# power_supply.net
KiCad netlist of a schematic drawn in Altium Designer
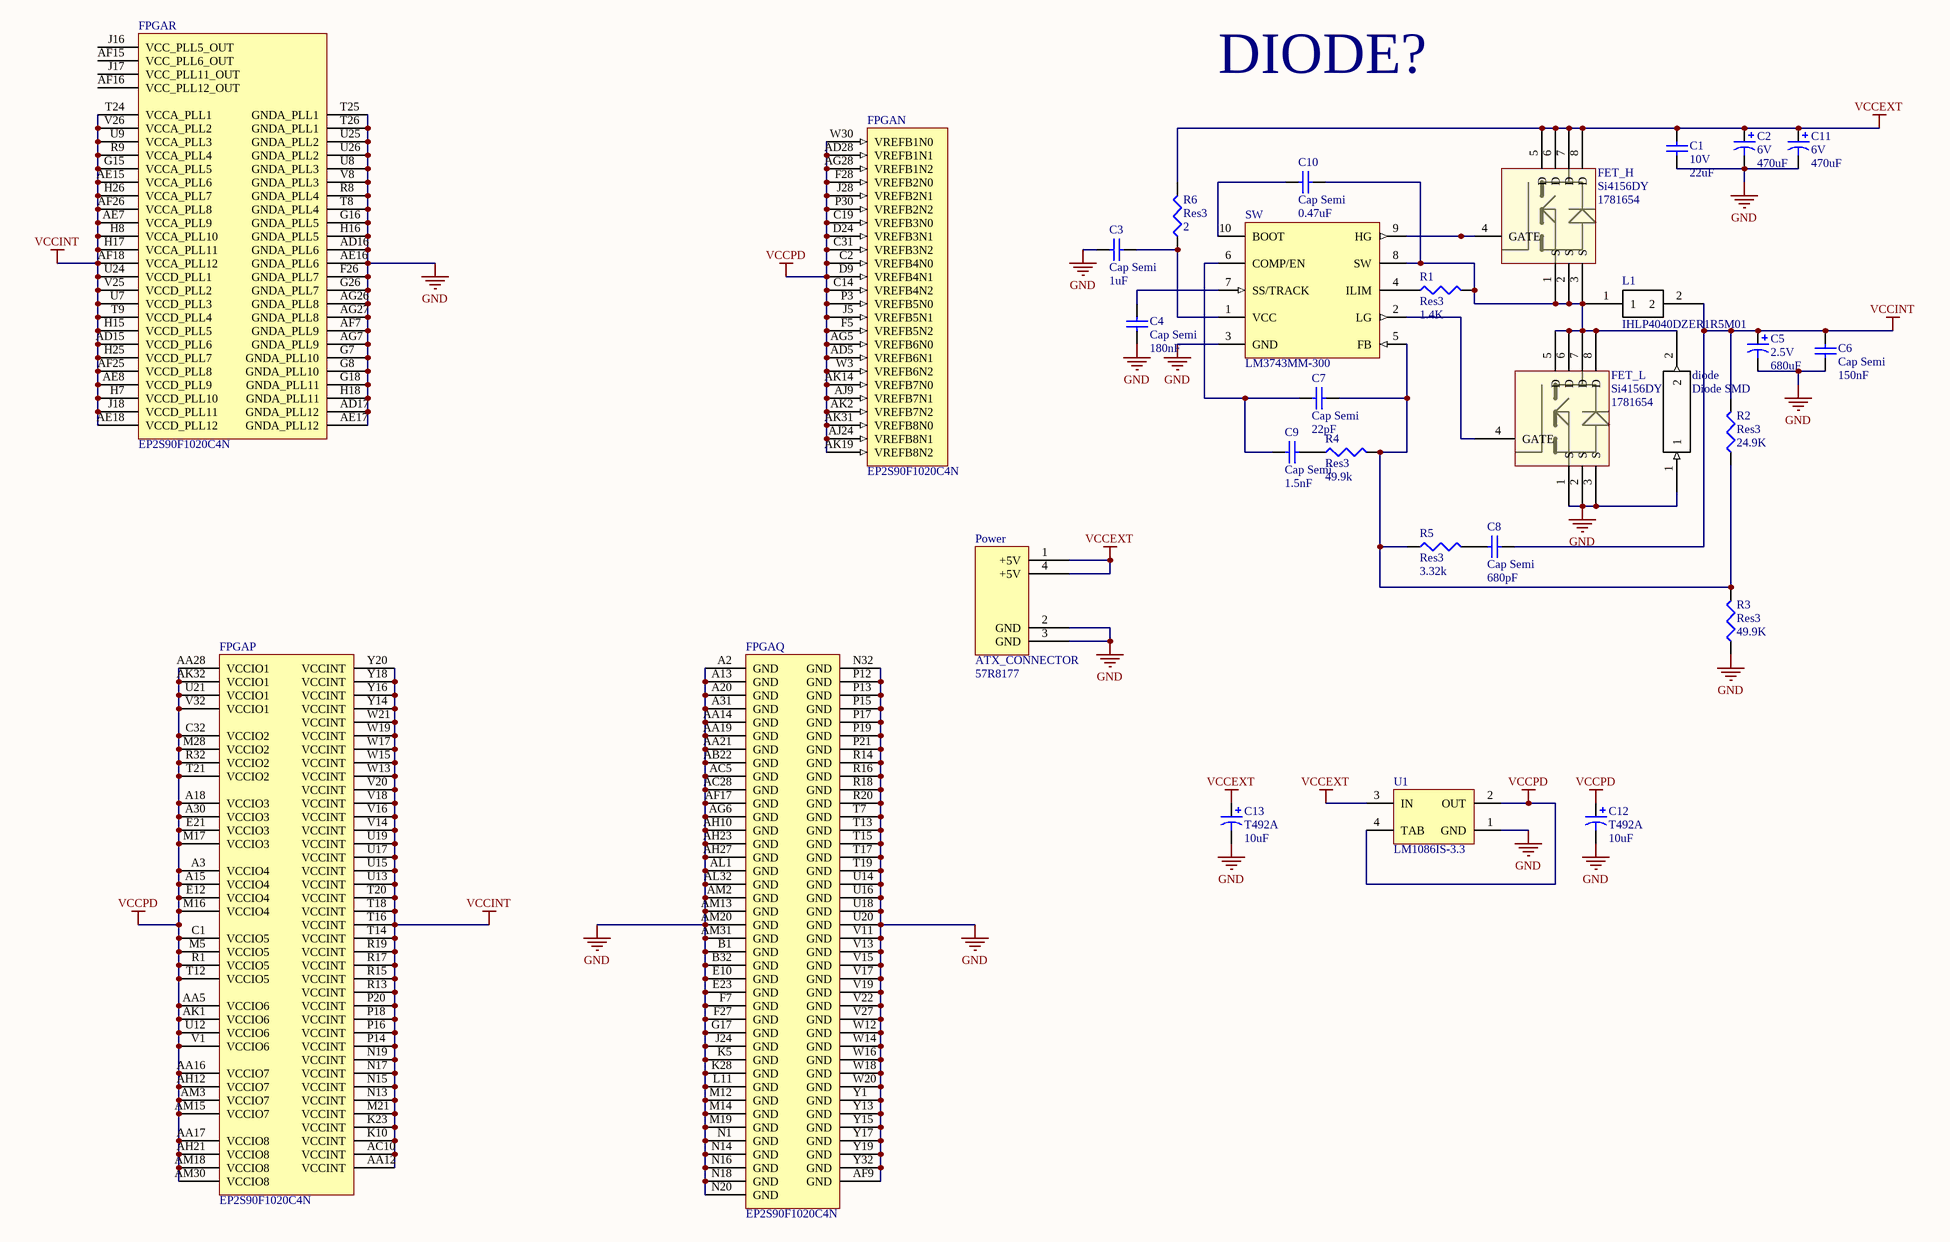
[diagram p0: power_supply.SchDoc]

(export (version "E")
  (design (tool "Eeschema 10.0.6"))
  (components
    (comp (ref "C1")
      (value "10V")
      (footprint "CAPC3225L")
      (description "Capacitor (Semiconductor SIM Model)")
      (fields (field (name "ALTIUM_VALUE") "22uF") (field (name "PUBLISHER") "Altium Limited"))
      (libsource (lib "Miscellaneous Devices") (part "Cap Semi"))
    )
    (comp (ref "C2")
      (value "6V")
      (footprint "KEMET Chip Capacitor:E")
      (description "Polarized Capacitor (Surface Mount)")
      (fields (field (name "ALTIUM_VALUE") "470uF") (field (name "PUBLISHER") "Altium Limited"))
      (libsource (lib "Miscellaneous Devices") (part "Cap Pol3"))
    )
    (comp (ref "C3")
      (value "Cap Semi")
      (footprint "2012[0805]")
      (description "Capacitor (Semiconductor SIM Model)")
      (fields (field (name "ALTIUM_VALUE") "1uF") (field (name "PUBLISHER") "Altium Limited"))
      (libsource (lib "Miscellaneous Devices") (part "Cap Semi"))
    )
    (comp (ref "C4")
      (value "Cap Semi")
      (footprint "2012[0805]")
      (description "Capacitor (Semiconductor SIM Model)")
      (fields (field (name "ALTIUM_VALUE") "180nF") (field (name "PUBLISHER") "Altium Limited"))
      (libsource (lib "Miscellaneous Devices") (part "Cap Semi"))
    )
    (comp (ref "C5")
      (value "2.5V")
      (footprint "E")
      (description "Polarized Capacitor (Surface Mount)")
      (fields (field (name "ALTIUM_VALUE") "680uF") (field (name "PUBLISHER") "Altium Limited"))
      (libsource (lib "Miscellaneous Devices") (part "Cap Pol3"))
    )
    (comp (ref "C6")
      (value "Cap Semi")
      (footprint "2012[0805]")
      (description "Capacitor (Semiconductor SIM Model)")
      (fields (field (name "ALTIUM_VALUE") "150nF") (field (name "PUBLISHER") "Altium Limited"))
      (libsource (lib "Miscellaneous Devices") (part "Cap Semi"))
    )
    (comp (ref "C7")
      (value "Cap Semi")
      (footprint "CAPC1608L")
      (description "Capacitor (Semiconductor SIM Model)")
      (fields (field (name "ALTIUM_VALUE") "22pF") (field (name "PUBLISHER") "Altium Limited"))
      (libsource (lib "Miscellaneous Devices") (part "Cap Semi"))
    )
    (comp (ref "C8")
      (value "Cap Semi")
      (footprint "CAPC1608L")
      (description "Capacitor (Semiconductor SIM Model)")
      (fields (field (name "ALTIUM_VALUE") "680pF") (field (name "PUBLISHER") "Altium Limited"))
      (libsource (lib "Miscellaneous Devices") (part "Cap Semi"))
    )
    (comp (ref "C9")
      (value "Cap Semi")
      (footprint "CAPC1608L")
      (description "Capacitor (Semiconductor SIM Model)")
      (fields (field (name "ALTIUM_VALUE") "1.5nF") (field (name "PUBLISHER") "Altium Limited"))
      (libsource (lib "Miscellaneous Devices") (part "Cap Semi"))
    )
    (comp (ref "C10")
      (value "Cap Semi")
      (footprint "2012[0805]")
      (description "Capacitor (Semiconductor SIM Model)")
      (fields (field (name "ALTIUM_VALUE") "0.47uF") (field (name "PUBLISHER") "Altium Limited"))
      (libsource (lib "Miscellaneous Devices") (part "Cap Semi"))
    )
    (comp (ref "C11")
      (value "6V")
      (footprint "E")
      (description "Polarized Capacitor (Surface Mount)")
      (fields (field (name "ALTIUM_VALUE") "470uF") (field (name "PUBLISHER") "Altium Limited"))
      (libsource (lib "Miscellaneous Devices") (part "Cap Pol3"))
    )
    (comp (ref "C12")
      (value "T492A")
      (footprint "A")
      (description "Solid Tantalum Chip Capacitor, T492 Series - CWR11 Style Per Mil-PRF-55365/8")
      (fields (field (name "ALTIUM_VALUE") "10uF") (field (name "PUBLISHER") "Altium Limited"))
      (libsource (lib "KEMET Chip Capacitor") (part "T492A"))
    )
    (comp (ref "C13")
      (value "T492A")
      (footprint "A")
      (description "Solid Tantalum Chip Capacitor, T492 Series - CWR11 Style Per Mil-PRF-55365/8")
      (fields (field (name "ALTIUM_VALUE") "10uF") (field (name "PUBLISHER") "Altium Limited"))
      (libsource (lib "KEMET Chip Capacitor") (part "T492A"))
    )
    (comp (ref "diode")
      (value "Diode SMD")
      (footprint "Diode SMD")
      (libsource (lib "Schematic Components") (part "Diode SMD"))
    )
    (comp (ref "FET_H")
      (value "Si4156DY")
      (footprint "SO-8C_M")
      (fields (field (name "SUPPLIER PART NUMBER 1") "1781654"))
      (libsource (lib "Schematic Components") (part "Si4156DY"))
    )
    (comp (ref "FET_L")
      (value "Si4156DY")
      (footprint "SO-8C_M")
      (fields (field (name "SUPPLIER PART NUMBER 1") "1781654"))
      (libsource (lib "Schematic Components") (part "Si4156DY"))
    )
    (comp (ref "FPGA")
      (value "EP2S90F1020C4N")
      (footprint "FBGA1020")
      (description "Stratix II 1.2V FPGA, 758 I/Os, 1020-Pin FineLine BGA, Speed Grade 4, Commercial Grade, Pb-Free")
      (fields (field (name "PUBLISHER") "Altium Limited"))
      (libsource (lib "Altera Stratix II") (part "EP2S90F1020C4N"))
    )
    (comp (ref "L1")
      (value "IHLP4040DZER1R5M01")
      (footprint "IHLP4040DZER1R5M01")
      (libsource (lib "Schematic Components") (part "IHLP4040DZER1R5M01"))
    )
    (comp (ref "Power")
      (value "ATX_CONNECTOR")
      (footprint "Molex 8981")
      (fields (field (name "SUPPLIER PART NUMBER 1") "57R8177"))
      (libsource (lib "Schematic Components") (part "ATX_CONNECTOR"))
    )
    (comp (ref "R1")
      (value "Res3")
      (footprint "RESC1608L")
      (description "Resistor")
      (fields (field (name "ALTIUM_VALUE") "1.4K") (field (name "PUBLISHER") "Altium Limited"))
      (libsource (lib "Miscellaneous Devices") (part "Res3"))
    )
    (comp (ref "R2")
      (value "Res3")
      (footprint "RESC1608L")
      (description "Resistor")
      (fields (field (name "ALTIUM_VALUE") "24.9K") (field (name "PUBLISHER") "Altium Limited"))
      (libsource (lib "Miscellaneous Devices") (part "Res3"))
    )
    (comp (ref "R3")
      (value "Res3")
      (footprint "RESC1608L")
      (description "Resistor")
      (fields (field (name "ALTIUM_VALUE") "49.9K") (field (name "PUBLISHER") "Altium Limited"))
      (libsource (lib "Miscellaneous Devices") (part "Res3"))
    )
    (comp (ref "R4")
      (value "Res3")
      (footprint "RESC1608L")
      (description "Resistor")
      (fields (field (name "ALTIUM_VALUE") "49.9k") (field (name "PUBLISHER") "Altium Limited"))
      (libsource (lib "Miscellaneous Devices") (part "Res3"))
    )
    (comp (ref "R5")
      (value "Res3")
      (footprint "RESC1608L")
      (description "Resistor")
      (fields (field (name "ALTIUM_VALUE") "3.32k") (field (name "PUBLISHER") "Altium Limited"))
      (libsource (lib "Miscellaneous Devices") (part "Res3"))
    )
    (comp (ref "R6")
      (value "Res3")
      (footprint "RESC1608L")
      (description "Resistor")
      (fields (field (name "ALTIUM_VALUE") "2") (field (name "PUBLISHER") "Altium Limited"))
      (libsource (lib "Miscellaneous Devices") (part "Res3"))
    )
    (comp (ref "SW")
      (value "LM3743MM-300")
      (footprint "MUB10A_N")
      (description "High-Performance Synchronous Buck Controller with Comprehensive Fault Protection Features")
      (fields
        (field (name "MANUFACTURER") "National Semiconductor")
        (field (name "DIGIKEYPARTNUMBER") "LM3743MM-300CT-ND")
        (field (name "PUBLISHER") "Altium Limited")
      )
      (libsource (lib "NSC Switcher") (part "LM3743MM-300"))
    )
    (comp (ref "U1")
      (value "LM1086IS-3.3")
      (footprint "TS3B_N")
      (description "1.5A Low Dropout Positive Regulators")
      (fields
        (field (name "MANUFACTURER") "National Semiconductor")
        (field (name "DIGIKEYPARTNUMBER") "LM1086IS-3.3-ND")
        (field (name "PUBLISHER") "Altium Limited")
      )
      (libsource (lib "NSC LDO") (part "LM1086IS-3.3"))
    )
  )
  (nets
    (net (code "1") (name "GND") (class "Default")
      (node (ref "C1") (pin "2") (pinfunction "2_2") (pintype "passive"))
      (node (ref "C11") (pin "2") (pinfunction "2_2") (pintype "passive"))
      (node (ref "C12") (pin "2") (pinfunction "2_2") (pintype "passive"))
      (node (ref "C13") (pin "2") (pinfunction "2_2") (pintype "passive"))
      (node (ref "C2") (pin "2") (pinfunction "2_2") (pintype "passive"))
      (node (ref "C3") (pin "2") (pinfunction "2_2") (pintype "passive"))
      (node (ref "C4") (pin "1") (pinfunction "1_1") (pintype "passive"))
      (node (ref "C5") (pin "2") (pinfunction "2_2") (pintype "passive"))
      (node (ref "C6") (pin "1") (pinfunction "1_1") (pintype "passive"))
      (node (ref "FET_L") (pin "1") (pinfunction "S_1") (pintype "passive"))
      (node (ref "FET_L") (pin "2") (pinfunction "S_2") (pintype "passive"))
      (node (ref "FET_L") (pin "3") (pinfunction "S_3") (pintype "passive"))
      (node (ref "FPGA") (pin "A13") (pinfunction "GND_A13") (pintype "power_in"))
      (node (ref "FPGA") (pin "A2") (pinfunction "GND_A2") (pintype "power_in"))
      (node (ref "FPGA") (pin "A20") (pinfunction "GND_A20") (pintype "power_in"))
      (node (ref "FPGA") (pin "A31") (pinfunction "GND_A31") (pintype "power_in"))
      (node (ref "FPGA") (pin "AA14") (pinfunction "GND_AA14") (pintype "power_in"))
      (node (ref "FPGA") (pin "AA19") (pinfunction "GND_AA19") (pintype "power_in"))
      (node (ref "FPGA") (pin "AA21") (pinfunction "GND_AA21") (pintype "power_in"))
      (node (ref "FPGA") (pin "AB22") (pinfunction "GND_AB22") (pintype "power_in"))
      (node (ref "FPGA") (pin "AC28") (pinfunction "GND_AC28") (pintype "power_in"))
      (node (ref "FPGA") (pin "AC5") (pinfunction "GND_AC5") (pintype "power_in"))
      (node (ref "FPGA") (pin "AD16") (pinfunction "GNDA_PLL6_AD16") (pintype "power_in"))
      (node (ref "FPGA") (pin "AD17") (pinfunction "GNDA_PLL12_AD17") (pintype "power_in"))
      (node (ref "FPGA") (pin "AE16") (pinfunction "GNDA_PLL6_AE16") (pintype "power_in"))
      (node (ref "FPGA") (pin "AE17") (pinfunction "GNDA_PLL12_AE17") (pintype "power_in"))
      (node (ref "FPGA") (pin "AF17") (pinfunction "GND_AF17") (pintype "power_in"))
      (node (ref "FPGA") (pin "AF7") (pinfunction "GNDA_PLL9_AF7") (pintype "power_in"))
      (node (ref "FPGA") (pin "AF9") (pinfunction "GND_AF9") (pintype "power_in"))
      (node (ref "FPGA") (pin "AG26") (pinfunction "GNDA_PLL8_AG26") (pintype "power_in"))
      (node (ref "FPGA") (pin "AG27") (pinfunction "GNDA_PLL8_AG27") (pintype "power_in"))
      (node (ref "FPGA") (pin "AG6") (pinfunction "GND_AG6") (pintype "power_in"))
      (node (ref "FPGA") (pin "AG7") (pinfunction "GNDA_PLL9_AG7") (pintype "power_in"))
      (node (ref "FPGA") (pin "AH10") (pinfunction "GND_AH10") (pintype "power_in"))
      (node (ref "FPGA") (pin "AH23") (pinfunction "GND_AH23") (pintype "power_in"))
      (node (ref "FPGA") (pin "AH27") (pinfunction "GND_AH27") (pintype "power_in"))
      (node (ref "FPGA") (pin "AL1") (pinfunction "GND_AL1") (pintype "power_in"))
      (node (ref "FPGA") (pin "AL32") (pinfunction "GND_AL32") (pintype "power_in"))
      (node (ref "FPGA") (pin "AM13") (pinfunction "GND_AM13") (pintype "power_in"))
      (node (ref "FPGA") (pin "AM2") (pinfunction "GND_AM2") (pintype "power_in"))
      (node (ref "FPGA") (pin "AM20") (pinfunction "GND_AM20") (pintype "power_in"))
      (node (ref "FPGA") (pin "AM31") (pinfunction "GND_AM31") (pintype "power_in"))
      (node (ref "FPGA") (pin "B1") (pinfunction "GND_B1") (pintype "power_in"))
      (node (ref "FPGA") (pin "B32") (pinfunction "GND_B32") (pintype "power_in"))
      (node (ref "FPGA") (pin "E10") (pinfunction "GND_E10") (pintype "power_in"))
      (node (ref "FPGA") (pin "E23") (pinfunction "GND_E23") (pintype "power_in"))
      (node (ref "FPGA") (pin "F26") (pinfunction "GNDA_PLL7_F26") (pintype "power_in"))
      (node (ref "FPGA") (pin "F27") (pinfunction "GND_F27") (pintype "power_in"))
      (node (ref "FPGA") (pin "F7") (pinfunction "GND_F7") (pintype "power_in"))
      (node (ref "FPGA") (pin "G16") (pinfunction "GNDA_PLL5_G16") (pintype "power_in"))
      (node (ref "FPGA") (pin "G17") (pinfunction "GND_G17") (pintype "power_in"))
      (node (ref "FPGA") (pin "G18") (pinfunction "GNDA_PLL11_G18") (pintype "power_in"))
      (node (ref "FPGA") (pin "G26") (pinfunction "GNDA_PLL7_G26") (pintype "power_in"))
      (node (ref "FPGA") (pin "G7") (pinfunction "GNDA_PLL10_G7") (pintype "power_in"))
      (node (ref "FPGA") (pin "G8") (pinfunction "GNDA_PLL10_G8") (pintype "power_in"))
      (node (ref "FPGA") (pin "H16") (pinfunction "GNDA_PLL5_H16") (pintype "power_in"))
      (node (ref "FPGA") (pin "H18") (pinfunction "GNDA_PLL11_H18") (pintype "power_in"))
      (node (ref "FPGA") (pin "J24") (pinfunction "GND_J24") (pintype "power_in"))
      (node (ref "FPGA") (pin "K28") (pinfunction "GND_K28") (pintype "power_in"))
      (node (ref "FPGA") (pin "K5") (pinfunction "GND_K5") (pintype "power_in"))
      (node (ref "FPGA") (pin "L11") (pinfunction "GND_L11") (pintype "power_in"))
      (node (ref "FPGA") (pin "M12") (pinfunction "GND_M12") (pintype "power_in"))
      (node (ref "FPGA") (pin "M14") (pinfunction "GND_M14") (pintype "power_in"))
      (node (ref "FPGA") (pin "M19") (pinfunction "GND_M19") (pintype "power_in"))
      (node (ref "FPGA") (pin "N1") (pinfunction "GND_N1") (pintype "power_in"))
      (node (ref "FPGA") (pin "N14") (pinfunction "GND_N14") (pintype "power_in"))
      (node (ref "FPGA") (pin "N16") (pinfunction "GND_N16") (pintype "power_in"))
      (node (ref "FPGA") (pin "N18") (pinfunction "GND_N18") (pintype "power_in"))
      (node (ref "FPGA") (pin "N20") (pinfunction "GND_N20") (pintype "power_in"))
      (node (ref "FPGA") (pin "N32") (pinfunction "GND_N32") (pintype "power_in"))
      (node (ref "FPGA") (pin "P12") (pinfunction "GND_P12") (pintype "power_in"))
      (node (ref "FPGA") (pin "P13") (pinfunction "GND_P13") (pintype "power_in"))
      (node (ref "FPGA") (pin "P15") (pinfunction "GND_P15") (pintype "power_in"))
      (node (ref "FPGA") (pin "P17") (pinfunction "GND_P17") (pintype "power_in"))
      (node (ref "FPGA") (pin "P19") (pinfunction "GND_P19") (pintype "power_in"))
      (node (ref "FPGA") (pin "P21") (pinfunction "GND_P21") (pintype "power_in"))
      (node (ref "FPGA") (pin "R14") (pinfunction "GND_R14") (pintype "power_in"))
      (node (ref "FPGA") (pin "R16") (pinfunction "GND_R16") (pintype "power_in"))
      (node (ref "FPGA") (pin "R18") (pinfunction "GND_R18") (pintype "power_in"))
      (node (ref "FPGA") (pin "R20") (pinfunction "GND_R20") (pintype "power_in"))
      (node (ref "FPGA") (pin "R8") (pinfunction "GNDA_PLL4_R8") (pintype "power_in"))
      (node (ref "FPGA") (pin "T13") (pinfunction "GND_T13") (pintype "power_in"))
      (node (ref "FPGA") (pin "T15") (pinfunction "GND_T15") (pintype "power_in"))
      (node (ref "FPGA") (pin "T17") (pinfunction "GND_T17") (pintype "power_in"))
      (node (ref "FPGA") (pin "T19") (pinfunction "GND_T19") (pintype "power_in"))
      (node (ref "FPGA") (pin "T25") (pinfunction "GNDA_PLL1_T25") (pintype "power_in"))
      (node (ref "FPGA") (pin "T26") (pinfunction "GNDA_PLL1_T26") (pintype "power_in"))
      (node (ref "FPGA") (pin "T7") (pinfunction "GND_T7") (pintype "power_in"))
      (node (ref "FPGA") (pin "T8") (pinfunction "GNDA_PLL4_T8") (pintype "power_in"))
      (node (ref "FPGA") (pin "U14") (pinfunction "GND_U14") (pintype "power_in"))
      (node (ref "FPGA") (pin "U16") (pinfunction "GND_U16") (pintype "power_in"))
      (node (ref "FPGA") (pin "U18") (pinfunction "GND_U18") (pintype "power_in"))
      (node (ref "FPGA") (pin "U20") (pinfunction "GND_U20") (pintype "power_in"))
      (node (ref "FPGA") (pin "U25") (pinfunction "GNDA_PLL2_U25") (pintype "power_in"))
      (node (ref "FPGA") (pin "U26") (pinfunction "GNDA_PLL2_U26") (pintype "power_in"))
      (node (ref "FPGA") (pin "U8") (pinfunction "GNDA_PLL3_U8") (pintype "power_in"))
      (node (ref "FPGA") (pin "V11") (pinfunction "GND_V11") (pintype "power_in"))
      (node (ref "FPGA") (pin "V13") (pinfunction "GND_V13") (pintype "power_in"))
      (node (ref "FPGA") (pin "V15") (pinfunction "GND_V15") (pintype "power_in"))
      (node (ref "FPGA") (pin "V17") (pinfunction "GND_V17") (pintype "power_in"))
      (node (ref "FPGA") (pin "V19") (pinfunction "GND_V19") (pintype "power_in"))
      (node (ref "FPGA") (pin "V22") (pinfunction "GND_V22") (pintype "power_in"))
      (node (ref "FPGA") (pin "V27") (pinfunction "GND_V27") (pintype "power_in"))
      (node (ref "FPGA") (pin "V8") (pinfunction "GNDA_PLL3_V8") (pintype "power_in"))
      (node (ref "FPGA") (pin "W12") (pinfunction "GND_W12") (pintype "power_in"))
      (node (ref "FPGA") (pin "W14") (pinfunction "GND_W14") (pintype "power_in"))
      (node (ref "FPGA") (pin "W16") (pinfunction "GND_W16") (pintype "power_in"))
      (node (ref "FPGA") (pin "W18") (pinfunction "GND_W18") (pintype "power_in"))
      (node (ref "FPGA") (pin "W20") (pinfunction "GND_W20") (pintype "power_in"))
      (node (ref "FPGA") (pin "Y1") (pinfunction "GND_Y1") (pintype "power_in"))
      (node (ref "FPGA") (pin "Y13") (pinfunction "GND_Y13") (pintype "power_in"))
      (node (ref "FPGA") (pin "Y15") (pinfunction "GND_Y15") (pintype "power_in"))
      (node (ref "FPGA") (pin "Y17") (pinfunction "GND_Y17") (pintype "power_in"))
      (node (ref "FPGA") (pin "Y19") (pinfunction "GND_Y19") (pintype "power_in"))
      (node (ref "FPGA") (pin "Y32") (pinfunction "GND_Y32") (pintype "power_in"))
      (node (ref "Power") (pin "2") (pinfunction "GND_2") (pintype "passive"))
      (node (ref "Power") (pin "3") (pinfunction "GND_3") (pintype "passive"))
      (node (ref "R3") (pin "1") (pinfunction "1_1") (pintype "passive"))
      (node (ref "SW") (pin "3") (pinfunction "GND_3") (pintype "power_in"))
      (node (ref "U1") (pin "1") (pinfunction "GND_1") (pintype "power_in"))
      (node (ref "diode") (pin "1") (pinfunction "1_1") (pintype "input"))
    )
    (net (code "2") (name "Net-(C8-Pad2)") (class "Default")
      (node (ref "C8") (pin "2") (pinfunction "2_2") (pintype "passive"))
      (node (ref "R5") (pin "2") (pinfunction "2_2") (pintype "passive"))
    )
    (net (code "3") (name "Net-(C9-Pad1)") (class "Default")
      (node (ref "C9") (pin "1") (pinfunction "1_1") (pintype "passive"))
      (node (ref "R4") (pin "1") (pinfunction "1_1") (pintype "passive"))
    )
    (net (code "4") (name "Net-(FET_H-GATE)") (class "Default")
      (node (ref "FET_H") (pin "4") (pinfunction "GATE_4") (pintype "passive"))
      (node (ref "SW") (pin "9") (pinfunction "HG_9") (pintype "output"))
    )
    (net (code "5") (name "Net-(FET_L-GATE)") (class "Default")
      (node (ref "FET_L") (pin "4") (pinfunction "GATE_4") (pintype "passive"))
      (node (ref "SW") (pin "2") (pinfunction "LG_2") (pintype "output"))
    )
    (net (code "6") (name "Net-(SW-BOOT)") (class "Default")
      (node (ref "C10") (pin "2") (pinfunction "2_2") (pintype "passive"))
      (node (ref "SW") (pin "10") (pinfunction "BOOT_10") (pintype "passive"))
    )
    (net (code "7") (name "Net-(SW-COMP{slash}EN)") (class "Default")
      (node (ref "C7") (pin "2") (pinfunction "2_2") (pintype "passive"))
      (node (ref "C9") (pin "2") (pinfunction "2_2") (pintype "passive"))
      (node (ref "SW") (pin "6") (pinfunction "COMP/EN_6") (pintype "passive"))
    )
    (net (code "8") (name "Net-(SW-FB)") (class "Default")
      (node (ref "C7") (pin "1") (pinfunction "1_1") (pintype "passive"))
      (node (ref "R2") (pin "1") (pinfunction "1_1") (pintype "passive"))
      (node (ref "R3") (pin "2") (pinfunction "2_2") (pintype "passive"))
      (node (ref "R4") (pin "2") (pinfunction "2_2") (pintype "passive"))
      (node (ref "R5") (pin "1") (pinfunction "1_1") (pintype "passive"))
      (node (ref "SW") (pin "5") (pinfunction "FB_5") (pintype "input"))
    )
    (net (code "9") (name "Net-(SW-ILIM)") (class "Default")
      (node (ref "R1") (pin "1") (pinfunction "1_1") (pintype "passive"))
      (node (ref "SW") (pin "4") (pinfunction "ILIM_4") (pintype "passive"))
    )
    (net (code "10") (name "Net-(SW-SS{slash}TRACK)") (class "Default")
      (node (ref "C4") (pin "2") (pinfunction "2_2") (pintype "passive"))
      (node (ref "SW") (pin "7") (pinfunction "SS/TRACK_7") (pintype "input"))
    )
    (net (code "11") (name "Net-(SW-SW)") (class "Default")
      (node (ref "C10") (pin "1") (pinfunction "1_1") (pintype "passive"))
      (node (ref "FET_H") (pin "1") (pinfunction "S_1") (pintype "passive"))
      (node (ref "FET_H") (pin "2") (pinfunction "S_2") (pintype "passive"))
      (node (ref "FET_H") (pin "3") (pinfunction "S_3") (pintype "passive"))
      (node (ref "FET_L") (pin "5") (pinfunction "D_5") (pintype "passive"))
      (node (ref "FET_L") (pin "6") (pinfunction "D_6") (pintype "passive"))
      (node (ref "FET_L") (pin "7") (pinfunction "D_7") (pintype "passive"))
      (node (ref "FET_L") (pin "8") (pinfunction "D_8") (pintype "passive"))
      (node (ref "L1") (pin "1") (pinfunction "1_1") (pintype "passive"))
      (node (ref "R1") (pin "2") (pinfunction "2_2") (pintype "passive"))
      (node (ref "SW") (pin "8") (pinfunction "SW_8") (pintype "power_in"))
      (node (ref "diode") (pin "2") (pinfunction "2_2") (pintype "output"))
    )
    (net (code "12") (name "Net-(SW-VCC)") (class "Default")
      (node (ref "C3") (pin "1") (pinfunction "1_1") (pintype "passive"))
      (node (ref "R6") (pin "1") (pinfunction "1_1") (pintype "passive"))
      (node (ref "SW") (pin "1") (pinfunction "VCC_1") (pintype "power_in"))
    )
    (net (code "13") (name "VCCEXT") (class "Default")
      (node (ref "C1") (pin "1") (pinfunction "1_1") (pintype "passive"))
      (node (ref "C11") (pin "1") (pinfunction "1_1") (pintype "passive"))
      (node (ref "C13") (pin "1") (pinfunction "1_1") (pintype "passive"))
      (node (ref "C2") (pin "1") (pinfunction "1_1") (pintype "passive"))
      (node (ref "FET_H") (pin "5") (pinfunction "D_5") (pintype "passive"))
      (node (ref "FET_H") (pin "6") (pinfunction "D_6") (pintype "passive"))
      (node (ref "FET_H") (pin "7") (pinfunction "D_7") (pintype "passive"))
      (node (ref "FET_H") (pin "8") (pinfunction "D_8") (pintype "passive"))
      (node (ref "Power") (pin "1") (pinfunction "+5V_1") (pintype "passive"))
      (node (ref "Power") (pin "4") (pinfunction "+5V_4") (pintype "passive"))
      (node (ref "R6") (pin "2") (pinfunction "2_2") (pintype "passive"))
      (node (ref "U1") (pin "3") (pinfunction "IN_3") (pintype "power_in"))
    )
    (net (code "14") (name "VCCINT") (class "Default")
      (node (ref "C5") (pin "1") (pinfunction "1_1") (pintype "passive"))
      (node (ref "C6") (pin "2") (pinfunction "2_2") (pintype "passive"))
      (node (ref "C8") (pin "1") (pinfunction "1_1") (pintype "passive"))
      (node (ref "FPGA") (pin "AA12") (pinfunction "VCCINT_AA12") (pintype "power_in"))
      (node (ref "FPGA") (pin "AC10") (pinfunction "VCCINT_AC10") (pintype "power_in"))
      (node (ref "FPGA") (pin "AD15") (pinfunction "VCCD_PLL6_AD15") (pintype "power_in"))
      (node (ref "FPGA") (pin "AE15") (pinfunction "VCCA_PLL6_AE15") (pintype "power_in"))
      (node (ref "FPGA") (pin "AE18") (pinfunction "VCCD_PLL12_AE18") (pintype "power_in"))
      (node (ref "FPGA") (pin "AE7") (pinfunction "VCCA_PLL9_AE7") (pintype "power_in"))
      (node (ref "FPGA") (pin "AE8") (pinfunction "VCCD_PLL9_AE8") (pintype "power_in"))
      (node (ref "FPGA") (pin "AF18") (pinfunction "VCCA_PLL12_AF18") (pintype "power_in"))
      (node (ref "FPGA") (pin "AF25") (pinfunction "VCCD_PLL8_AF25") (pintype "power_in"))
      (node (ref "FPGA") (pin "AF26") (pinfunction "VCCA_PLL8_AF26") (pintype "power_in"))
      (node (ref "FPGA") (pin "G15") (pinfunction "VCCA_PLL5_G15") (pintype "power_in"))
      (node (ref "FPGA") (pin "H15") (pinfunction "VCCD_PLL5_H15") (pintype "power_in"))
      (node (ref "FPGA") (pin "H17") (pinfunction "VCCA_PLL11_H17") (pintype "power_in"))
      (node (ref "FPGA") (pin "H25") (pinfunction "VCCD_PLL7_H25") (pintype "power_in"))
      (node (ref "FPGA") (pin "H26") (pinfunction "VCCA_PLL7_H26") (pintype "power_in"))
      (node (ref "FPGA") (pin "H7") (pinfunction "VCCD_PLL10_H7") (pintype "power_in"))
      (node (ref "FPGA") (pin "H8") (pinfunction "VCCA_PLL10_H8") (pintype "power_in"))
      (node (ref "FPGA") (pin "J18") (pinfunction "VCCD_PLL11_J18") (pintype "power_in"))
      (node (ref "FPGA") (pin "K10") (pinfunction "VCCINT_K10") (pintype "power_in"))
      (node (ref "FPGA") (pin "K23") (pinfunction "VCCINT_K23") (pintype "power_in"))
      (node (ref "FPGA") (pin "M21") (pinfunction "VCCINT_M21") (pintype "power_in"))
      (node (ref "FPGA") (pin "N13") (pinfunction "VCCINT_N13") (pintype "power_in"))
      (node (ref "FPGA") (pin "N15") (pinfunction "VCCINT_N15") (pintype "power_in"))
      (node (ref "FPGA") (pin "N17") (pinfunction "VCCINT_N17") (pintype "power_in"))
      (node (ref "FPGA") (pin "N19") (pinfunction "VCCINT_N19") (pintype "power_in"))
      (node (ref "FPGA") (pin "P14") (pinfunction "VCCINT_P14") (pintype "power_in"))
      (node (ref "FPGA") (pin "P16") (pinfunction "VCCINT_P16") (pintype "power_in"))
      (node (ref "FPGA") (pin "P18") (pinfunction "VCCINT_P18") (pintype "power_in"))
      (node (ref "FPGA") (pin "P20") (pinfunction "VCCINT_P20") (pintype "power_in"))
      (node (ref "FPGA") (pin "R13") (pinfunction "VCCINT_R13") (pintype "power_in"))
      (node (ref "FPGA") (pin "R15") (pinfunction "VCCINT_R15") (pintype "power_in"))
      (node (ref "FPGA") (pin "R17") (pinfunction "VCCINT_R17") (pintype "power_in"))
      (node (ref "FPGA") (pin "R19") (pinfunction "VCCINT_R19") (pintype "power_in"))
      (node (ref "FPGA") (pin "R9") (pinfunction "VCCA_PLL4_R9") (pintype "power_in"))
      (node (ref "FPGA") (pin "T14") (pinfunction "VCCINT_T14") (pintype "power_in"))
      (node (ref "FPGA") (pin "T16") (pinfunction "VCCINT_T16") (pintype "power_in"))
      (node (ref "FPGA") (pin "T18") (pinfunction "VCCINT_T18") (pintype "power_in"))
      (node (ref "FPGA") (pin "T20") (pinfunction "VCCINT_T20") (pintype "power_in"))
      (node (ref "FPGA") (pin "T24") (pinfunction "VCCA_PLL1_T24") (pintype "power_in"))
      (node (ref "FPGA") (pin "T9") (pinfunction "VCCD_PLL4_T9") (pintype "power_in"))
      (node (ref "FPGA") (pin "U13") (pinfunction "VCCINT_U13") (pintype "power_in"))
      (node (ref "FPGA") (pin "U15") (pinfunction "VCCINT_U15") (pintype "power_in"))
      (node (ref "FPGA") (pin "U17") (pinfunction "VCCINT_U17") (pintype "power_in"))
      (node (ref "FPGA") (pin "U19") (pinfunction "VCCINT_U19") (pintype "power_in"))
      (node (ref "FPGA") (pin "U24") (pinfunction "VCCD_PLL1_U24") (pintype "power_in"))
      (node (ref "FPGA") (pin "U7") (pinfunction "VCCD_PLL3_U7") (pintype "power_in"))
      (node (ref "FPGA") (pin "U9") (pinfunction "VCCA_PLL3_U9") (pintype "power_in"))
      (node (ref "FPGA") (pin "V14") (pinfunction "VCCINT_V14") (pintype "power_in"))
      (node (ref "FPGA") (pin "V16") (pinfunction "VCCINT_V16") (pintype "power_in"))
      (node (ref "FPGA") (pin "V18") (pinfunction "VCCINT_V18") (pintype "power_in"))
      (node (ref "FPGA") (pin "V20") (pinfunction "VCCINT_V20") (pintype "power_in"))
      (node (ref "FPGA") (pin "V25") (pinfunction "VCCD_PLL2_V25") (pintype "power_in"))
      (node (ref "FPGA") (pin "V26") (pinfunction "VCCA_PLL2_V26") (pintype "power_in"))
      (node (ref "FPGA") (pin "W13") (pinfunction "VCCINT_W13") (pintype "power_in"))
      (node (ref "FPGA") (pin "W15") (pinfunction "VCCINT_W15") (pintype "power_in"))
      (node (ref "FPGA") (pin "W17") (pinfunction "VCCINT_W17") (pintype "power_in"))
      (node (ref "FPGA") (pin "W19") (pinfunction "VCCINT_W19") (pintype "power_in"))
      (node (ref "FPGA") (pin "W21") (pinfunction "VCCINT_W21") (pintype "power_in"))
      (node (ref "FPGA") (pin "Y14") (pinfunction "VCCINT_Y14") (pintype "power_in"))
      (node (ref "FPGA") (pin "Y16") (pinfunction "VCCINT_Y16") (pintype "power_in"))
      (node (ref "FPGA") (pin "Y18") (pinfunction "VCCINT_Y18") (pintype "power_in"))
      (node (ref "FPGA") (pin "Y20") (pinfunction "VCCINT_Y20") (pintype "power_in"))
      (node (ref "L1") (pin "2") (pinfunction "2_2") (pintype "passive"))
      (node (ref "R2") (pin "2") (pinfunction "2_2") (pintype "passive"))
    )
    (net (code "15") (name "VCCPD") (class "Default")
      (node (ref "C12") (pin "1") (pinfunction "1_1") (pintype "passive"))
      (node (ref "FPGA") (pin "A15") (pinfunction "VCCIO4_A15") (pintype "power_in"))
      (node (ref "FPGA") (pin "A18") (pinfunction "VCCIO3_A18") (pintype "power_in"))
      (node (ref "FPGA") (pin "A3") (pinfunction "VCCIO4_A3") (pintype "power_in"))
      (node (ref "FPGA") (pin "A30") (pinfunction "VCCIO3_A30") (pintype "power_in"))
      (node (ref "FPGA") (pin "AA16") (pinfunction "VCCIO7_AA16") (pintype "power_in"))
      (node (ref "FPGA") (pin "AA17") (pinfunction "VCCIO8_AA17") (pintype "power_in"))
      (node (ref "FPGA") (pin "AA28") (pinfunction "VCCIO1_AA28") (pintype "power_in"))
      (node (ref "FPGA") (pin "AA5") (pinfunction "VCCIO6_AA5") (pintype "power_in"))
      (node (ref "FPGA") (pin "AD28") (pinfunction "VREFB1N1_AD28") (pintype "input"))
      (node (ref "FPGA") (pin "AD5") (pinfunction "VREFB6N1_AD5") (pintype "input"))
      (node (ref "FPGA") (pin "AG28") (pinfunction "VREFB1N2_AG28") (pintype "input"))
      (node (ref "FPGA") (pin "AG5") (pinfunction "VREFB6N0_AG5") (pintype "input"))
      (node (ref "FPGA") (pin "AH12") (pinfunction "VCCIO7_AH12") (pintype "power_in"))
      (node (ref "FPGA") (pin "AH21") (pinfunction "VCCIO8_AH21") (pintype "power_in"))
      (node (ref "FPGA") (pin "AJ24") (pinfunction "VREFB8N1_AJ24") (pintype "input"))
      (node (ref "FPGA") (pin "AJ9") (pinfunction "VREFB7N1_AJ9") (pintype "input"))
      (node (ref "FPGA") (pin "AK1") (pinfunction "VCCIO6_AK1") (pintype "power_in"))
      (node (ref "FPGA") (pin "AK14") (pinfunction "VREFB7N0_AK14") (pintype "input"))
      (node (ref "FPGA") (pin "AK19") (pinfunction "VREFB8N2_AK19") (pintype "input"))
      (node (ref "FPGA") (pin "AK2") (pinfunction "VREFB7N2_AK2") (pintype "input"))
      (node (ref "FPGA") (pin "AK31") (pinfunction "VREFB8N0_AK31") (pintype "input"))
      (node (ref "FPGA") (pin "AK32") (pinfunction "VCCIO1_AK32") (pintype "power_in"))
      (node (ref "FPGA") (pin "AM15") (pinfunction "VCCIO7_AM15") (pintype "power_in"))
      (node (ref "FPGA") (pin "AM18") (pinfunction "VCCIO8_AM18") (pintype "power_in"))
      (node (ref "FPGA") (pin "AM3") (pinfunction "VCCIO7_AM3") (pintype "power_in"))
      (node (ref "FPGA") (pin "AM30") (pinfunction "VCCIO8_AM30") (pintype "power_in"))
      (node (ref "FPGA") (pin "C1") (pinfunction "VCCIO5_C1") (pintype "power_in"))
      (node (ref "FPGA") (pin "C14") (pinfunction "VREFB4N2_C14") (pintype "input"))
      (node (ref "FPGA") (pin "C19") (pinfunction "VREFB3N0_C19") (pintype "input"))
      (node (ref "FPGA") (pin "C2") (pinfunction "VREFB4N0_C2") (pintype "input"))
      (node (ref "FPGA") (pin "C31") (pinfunction "VREFB3N2_C31") (pintype "input"))
      (node (ref "FPGA") (pin "C32") (pinfunction "VCCIO2_C32") (pintype "power_in"))
      (node (ref "FPGA") (pin "D24") (pinfunction "VREFB3N1_D24") (pintype "input"))
      (node (ref "FPGA") (pin "D9") (pinfunction "VREFB4N1_D9") (pintype "input"))
      (node (ref "FPGA") (pin "E12") (pinfunction "VCCIO4_E12") (pintype "power_in"))
      (node (ref "FPGA") (pin "E21") (pinfunction "VCCIO3_E21") (pintype "power_in"))
      (node (ref "FPGA") (pin "F28") (pinfunction "VREFB2N0_F28") (pintype "input"))
      (node (ref "FPGA") (pin "F5") (pinfunction "VREFB5N2_F5") (pintype "input"))
      (node (ref "FPGA") (pin "J28") (pinfunction "VREFB2N1_J28") (pintype "input"))
      (node (ref "FPGA") (pin "J5") (pinfunction "VREFB5N1_J5") (pintype "input"))
      (node (ref "FPGA") (pin "M16") (pinfunction "VCCIO4_M16") (pintype "power_in"))
      (node (ref "FPGA") (pin "M17") (pinfunction "VCCIO3_M17") (pintype "power_in"))
      (node (ref "FPGA") (pin "M28") (pinfunction "VCCIO2_M28") (pintype "power_in"))
      (node (ref "FPGA") (pin "M5") (pinfunction "VCCIO5_M5") (pintype "power_in"))
      (node (ref "FPGA") (pin "P3") (pinfunction "VREFB5N0_P3") (pintype "input"))
      (node (ref "FPGA") (pin "P30") (pinfunction "VREFB2N2_P30") (pintype "input"))
      (node (ref "FPGA") (pin "R1") (pinfunction "VCCIO5_R1") (pintype "power_in"))
      (node (ref "FPGA") (pin "R32") (pinfunction "VCCIO2_R32") (pintype "power_in"))
      (node (ref "FPGA") (pin "T12") (pinfunction "VCCIO5_T12") (pintype "power_in"))
      (node (ref "FPGA") (pin "T21") (pinfunction "VCCIO2_T21") (pintype "power_in"))
      (node (ref "FPGA") (pin "U12") (pinfunction "VCCIO6_U12") (pintype "power_in"))
      (node (ref "FPGA") (pin "U21") (pinfunction "VCCIO1_U21") (pintype "power_in"))
      (node (ref "FPGA") (pin "V1") (pinfunction "VCCIO6_V1") (pintype "power_in"))
      (node (ref "FPGA") (pin "V32") (pinfunction "VCCIO1_V32") (pintype "power_in"))
      (node (ref "FPGA") (pin "W3") (pinfunction "VREFB6N2_W3") (pintype "input"))
      (node (ref "FPGA") (pin "W30") (pinfunction "VREFB1N0_W30") (pintype "input"))
      (node (ref "U1") (pin "2") (pinfunction "OUT_2") (pintype "power_in"))
      (node (ref "U1") (pin "4") (pinfunction "TAB_4") (pintype "power_in"))
    )
    (net (code "16") (name "unconnected-(FPGAR-VCC_PLL5_OUT-PadJ16)") (class "Default")
      (node (ref "FPGA") (pin "J16") (pinfunction "VCC_PLL5_OUT_J16") (pintype "power_in"))
    )
    (net (code "17") (name "unconnected-(FPGAR-VCC_PLL6_OUT-PadAF15)") (class "Default")
      (node (ref "FPGA") (pin "AF15") (pinfunction "VCC_PLL6_OUT_AF15") (pintype "power_in"))
    )
    (net (code "18") (name "unconnected-(FPGAR-VCC_PLL11_OUT-PadJ17)") (class "Default")
      (node (ref "FPGA") (pin "J17") (pinfunction "VCC_PLL11_OUT_J17") (pintype "power_in"))
    )
    (net (code "19") (name "unconnected-(FPGAR-VCC_PLL12_OUT-PadAF16)") (class "Default")
      (node (ref "FPGA") (pin "AF16") (pinfunction "VCC_PLL12_OUT_AF16") (pintype "power_in"))
    )
  )
)
